# indicator.net
KiCad netlist of a schematic drawn in EAGLE
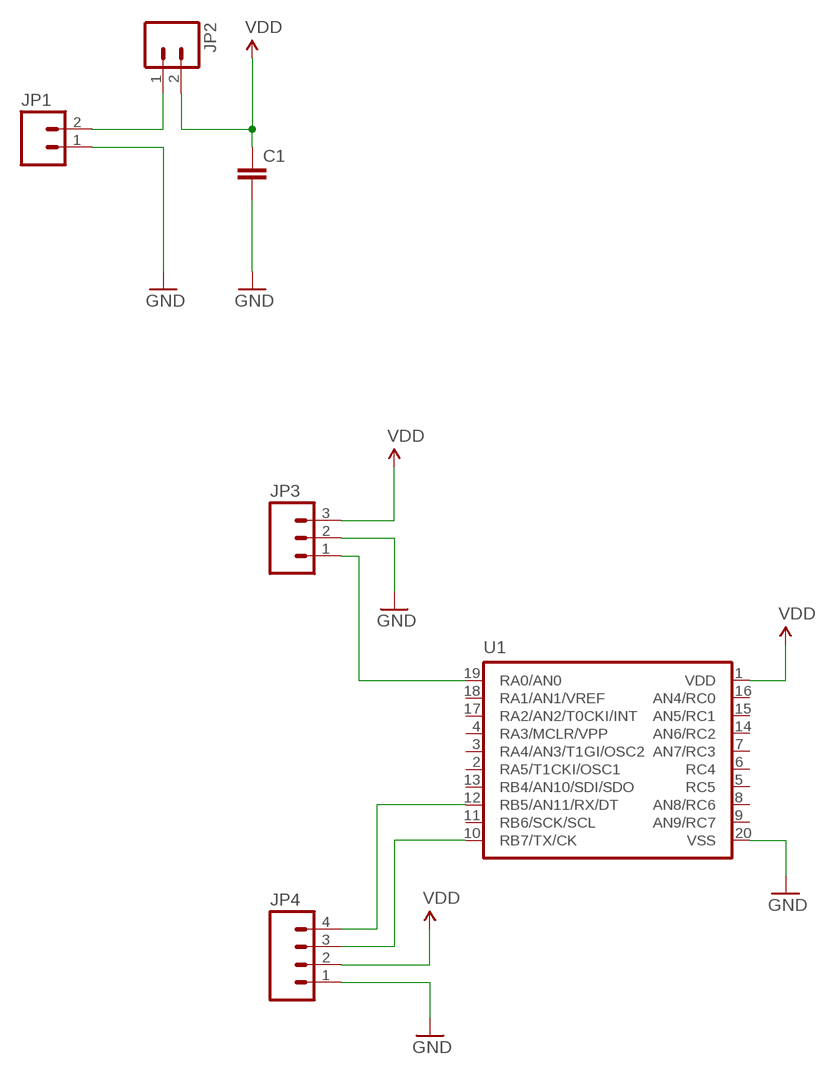
[diagram p0: schematic, sheet 1]

(export (version "E")
  (design (tool "Eeschema 10.0.6"))
  (components
    (comp (ref "C1")
      (value "CAPPTH1")
      (footprint "eagle-import:CAP-PTH-5MM")
      (libsource (lib "eagle-import") (part "CAPPTH1"))
    )
    (comp (ref "JP1")
      (value "M02PTH")
      (footprint "eagle-import:1X02")
      (libsource (lib "eagle-import") (part "M02PTH"))
    )
    (comp (ref "JP2")
      (value "M02PTH")
      (footprint "eagle-import:1X02")
      (libsource (lib "eagle-import") (part "M02PTH"))
    )
    (comp (ref "JP3")
      (value "M03PTH")
      (footprint "eagle-import:1X03")
      (libsource (lib "eagle-import") (part "M03PTH"))
    )
    (comp (ref "JP4")
      (value "M04PTH")
      (footprint "eagle-import:1X04")
      (libsource (lib "eagle-import") (part "M04PTH"))
    )
    (comp (ref "U1")
      (value "PIC16F6XX")
      (footprint "eagle-import:DIL20")
      (libsource (lib "eagle-import") (part "PIC16F6XX"))
    )
  )
  (nets
    (net (code "1") (name "GND") (class "Default")
      (node (ref "C1") (pin "2") (pinfunction "2_2") (pintype "passive"))
      (node (ref "JP1") (pin "1") (pinfunction "1_1") (pintype "passive"))
      (node (ref "JP3") (pin "2") (pinfunction "2_2") (pintype "passive"))
      (node (ref "JP4") (pin "1") (pinfunction "1_1") (pintype "passive"))
      (node (ref "U1") (pin "20") (pinfunction "VSS_20") (pintype "power_in"))
    )
    (net (code "2") (name "Net-(JP1-Pad2)") (class "Default")
      (node (ref "JP1") (pin "2") (pinfunction "2_2") (pintype "passive"))
      (node (ref "JP2") (pin "1") (pinfunction "1_1") (pintype "passive"))
    )
    (net (code "3") (name "Net-(U1-RA0{slash}AN0)") (class "Default")
      (node (ref "JP3") (pin "1") (pinfunction "1_1") (pintype "passive"))
      (node (ref "U1") (pin "19") (pinfunction "RA0/AN0_19") (pintype "bidirectional"))
    )
    (net (code "4") (name "Net-(U1-RB5{slash}AN11{slash}RX{slash}DT)") (class "Default")
      (node (ref "JP4") (pin "4") (pinfunction "4_4") (pintype "passive"))
      (node (ref "U1") (pin "12") (pinfunction "RB5/AN11/RX/DT_12") (pintype "bidirectional"))
    )
    (net (code "5") (name "Net-(U1-RB7{slash}TX{slash}CK)") (class "Default")
      (node (ref "JP4") (pin "3") (pinfunction "3_3") (pintype "passive"))
      (node (ref "U1") (pin "10") (pinfunction "RB7/TX/CK_10") (pintype "bidirectional"))
    )
    (net (code "6") (name "VDD") (class "Default")
      (node (ref "C1") (pin "1") (pinfunction "1_1") (pintype "passive"))
      (node (ref "JP2") (pin "2") (pinfunction "2_2") (pintype "passive"))
      (node (ref "JP3") (pin "3") (pinfunction "3_3") (pintype "passive"))
      (node (ref "JP4") (pin "2") (pinfunction "2_2") (pintype "passive"))
      (node (ref "U1") (pin "1") (pinfunction "VDD_1") (pintype "power_in"))
    )
    (net (code "7") (name "unconnected-(U1-AN4{slash}RC0-Pad16)") (class "Default")
      (node (ref "U1") (pin "16") (pinfunction "AN4/RC0_16") (pintype "bidirectional"))
    )
    (net (code "8") (name "unconnected-(U1-AN5{slash}RC1-Pad15)") (class "Default")
      (node (ref "U1") (pin "15") (pinfunction "AN5/RC1_15") (pintype "bidirectional"))
    )
    (net (code "9") (name "unconnected-(U1-AN6{slash}RC2-Pad14)") (class "Default")
      (node (ref "U1") (pin "14") (pinfunction "AN6/RC2_14") (pintype "bidirectional"))
    )
    (net (code "10") (name "unconnected-(U1-AN7{slash}RC3-Pad7)") (class "Default")
      (node (ref "U1") (pin "7") (pinfunction "AN7/RC3_7") (pintype "bidirectional"))
    )
    (net (code "11") (name "unconnected-(U1-AN8{slash}RC6-Pad8)") (class "Default")
      (node (ref "U1") (pin "8") (pinfunction "AN8/RC6_8") (pintype "bidirectional"))
    )
    (net (code "12") (name "unconnected-(U1-AN9{slash}RC7-Pad9)") (class "Default")
      (node (ref "U1") (pin "9") (pinfunction "AN9/RC7_9") (pintype "bidirectional"))
    )
    (net (code "13") (name "unconnected-(U1-RA1{slash}AN1{slash}VREF-Pad18)") (class "Default")
      (node (ref "U1") (pin "18") (pinfunction "RA1/AN1/VREF_18") (pintype "bidirectional"))
    )
    (net (code "14") (name "unconnected-(U1-RA2{slash}AN2{slash}T0CKI{slash}INT-Pad17)") (class "Default")
      (node (ref "U1") (pin "17") (pinfunction "RA2/AN2/T0CKI/INT_17") (pintype "bidirectional"))
    )
    (net (code "15") (name "unconnected-(U1-RA3{slash}MCLR{slash}VPP-Pad4)") (class "Default")
      (node (ref "U1") (pin "4") (pinfunction "RA3/MCLR/VPP_4") (pintype "input"))
    )
    (net (code "16") (name "unconnected-(U1-RA4{slash}AN3{slash}T1GI{slash}OSC2-Pad3)") (class "Default")
      (node (ref "U1") (pin "3") (pinfunction "RA4/AN3/T1GI/OSC2_3") (pintype "bidirectional"))
    )
    (net (code "17") (name "unconnected-(U1-RA5{slash}T1CKI{slash}OSC1-Pad2)") (class "Default")
      (node (ref "U1") (pin "2") (pinfunction "RA5/T1CKI/OSC1_2") (pintype "bidirectional"))
    )
    (net (code "18") (name "unconnected-(U1-RB4{slash}AN10{slash}SDI{slash}SDO-Pad13)") (class "Default")
      (node (ref "U1") (pin "13") (pinfunction "RB4/AN10/SDI/SDO_13") (pintype "bidirectional"))
    )
    (net (code "19") (name "unconnected-(U1-RB6{slash}SCK{slash}SCL-Pad11)") (class "Default")
      (node (ref "U1") (pin "11") (pinfunction "RB6/SCK/SCL_11") (pintype "bidirectional"))
    )
    (net (code "20") (name "unconnected-(U1-RC4-Pad6)") (class "Default")
      (node (ref "U1") (pin "6") (pinfunction "RC4_6") (pintype "bidirectional"))
    )
    (net (code "21") (name "unconnected-(U1-RC5-Pad5)") (class "Default")
      (node (ref "U1") (pin "5") (pinfunction "RC5_5") (pintype "bidirectional"))
    )
  )
)
